# eBOOK_v33.net
KiCad netlist of a schematic drawn in EAGLE
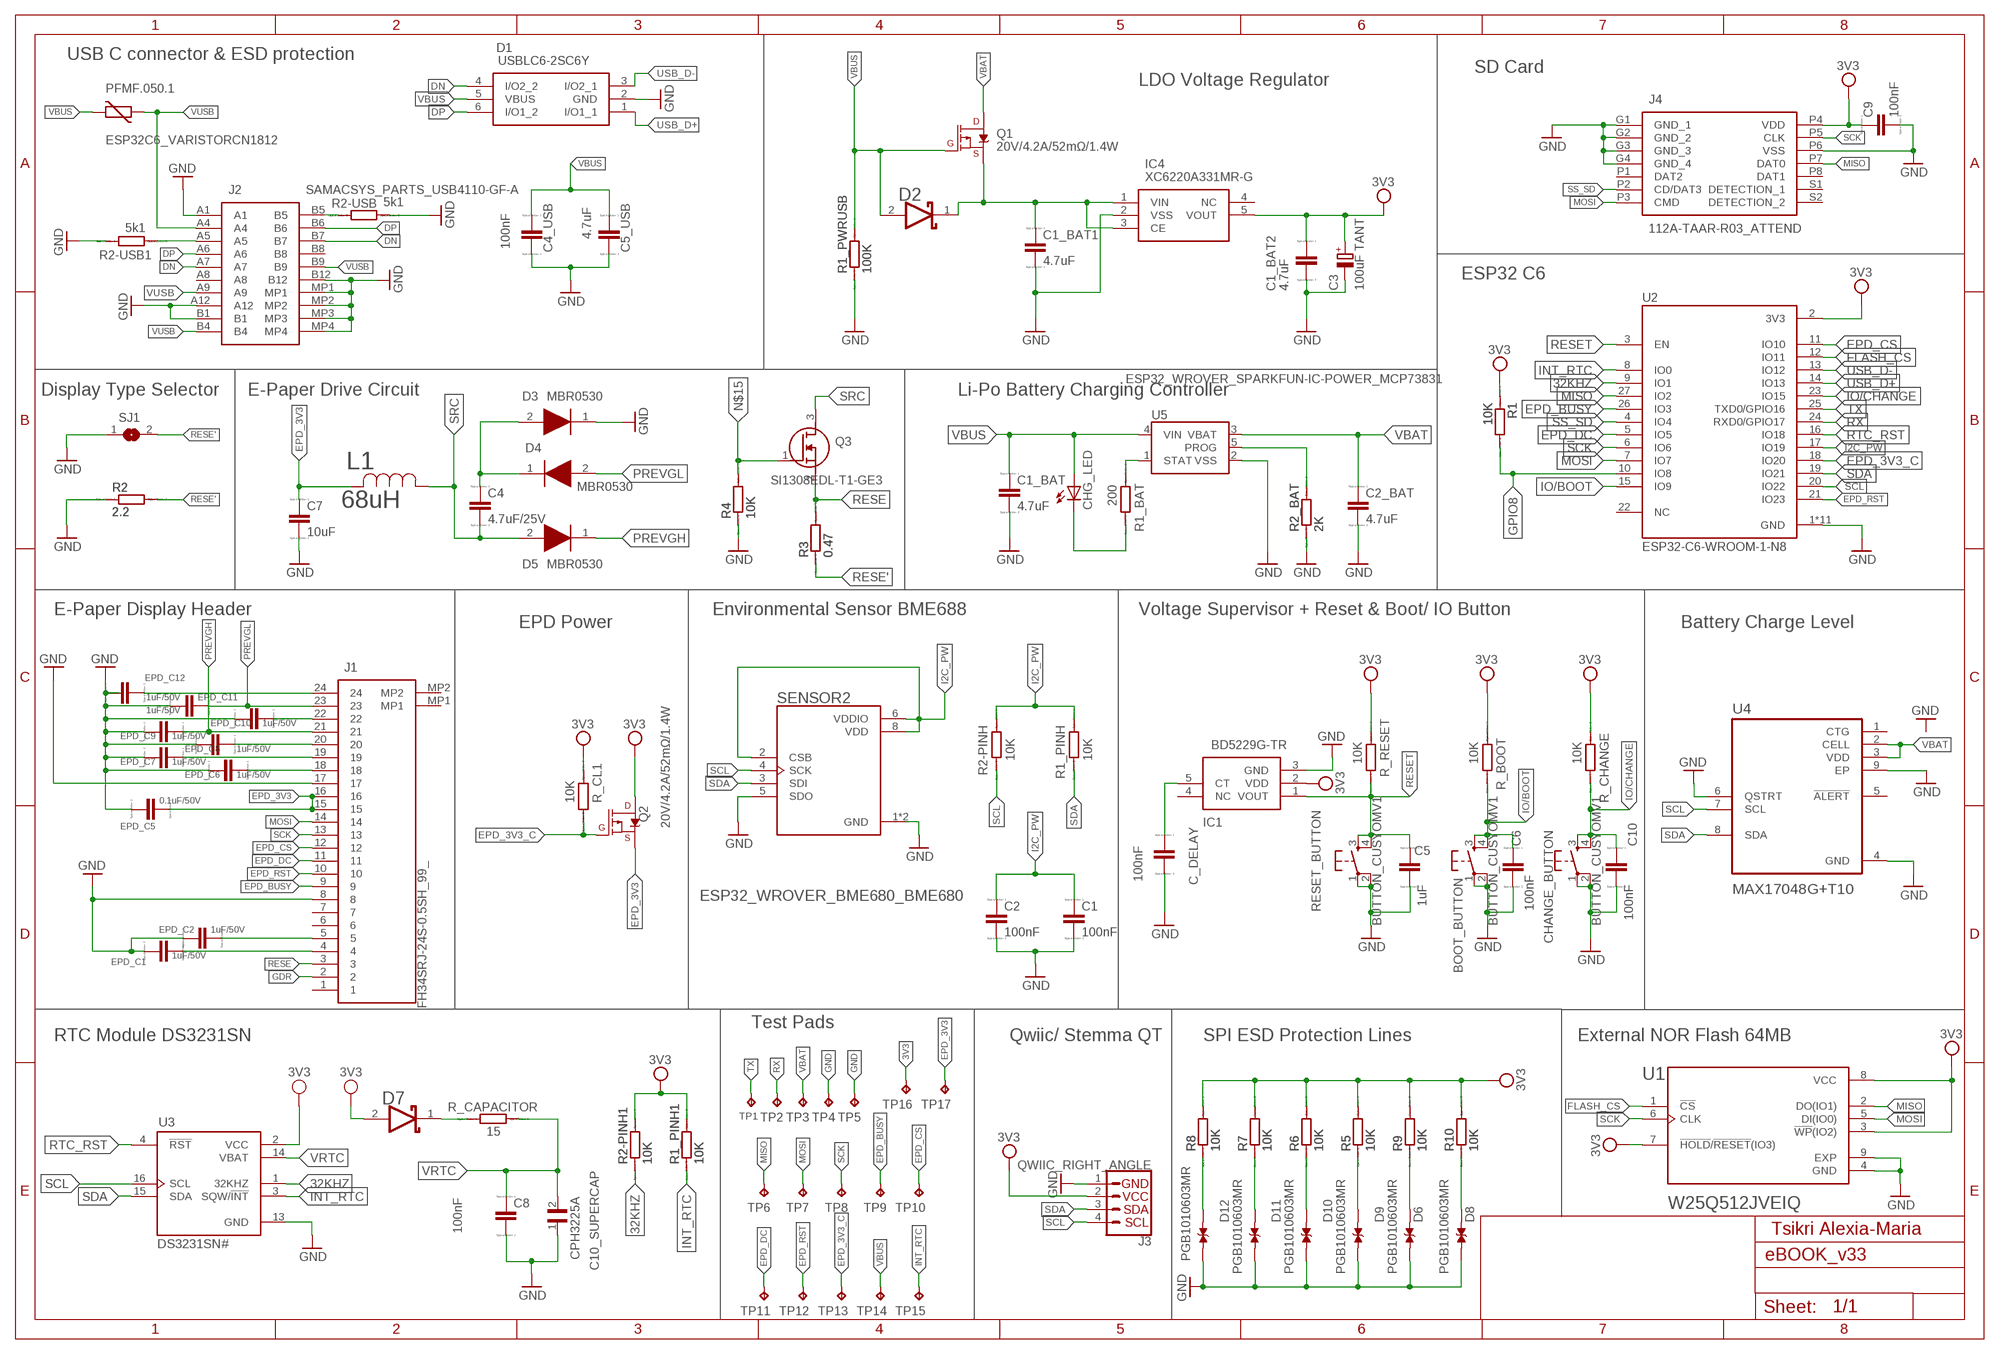
[diagram p0: schematic, sheet 1]

(export (version "E")
  (design (tool "Eeschema 10.0.6"))
  (components
    (comp (ref "BOOT_BUTTON")
      (value "BUTTON_CUSYOMV1")
      (footprint "eagle-import:MYBUTTON")
      (libsource (lib "eagle-import") (part "BUTTON_CUSYOMV1"))
    )
    (comp (ref "C1")
      (value "100nF")
      (footprint "eagle-import:ESP32_WROVER_EAGLE-LTSPICE_C0402")
      (libsource (lib "eagle-import") (part "ESP32_WROVER_EAGLE-LTSPICE_CC0402"))
    )
    (comp (ref "C1_BAT")
      (value "4.7uF")
      (footprint "eagle-import:ESP32_WROVER_EAGLE-LTSPICE_C0402")
      (libsource (lib "eagle-import") (part "ESP32_WROVER_EAGLE-LTSPICE_CC0402"))
    )
    (comp (ref "C1_BAT1")
      (value "4.7uF")
      (footprint "eagle-import:ESP32_WROVER_EAGLE-LTSPICE_C0402")
      (libsource (lib "eagle-import") (part "ESP32_WROVER_EAGLE-LTSPICE_CC0402"))
    )
    (comp (ref "C1_BAT2")
      (value "4.7uF")
      (footprint "eagle-import:ESP32_WROVER_EAGLE-LTSPICE_C0402")
      (libsource (lib "eagle-import") (part "ESP32_WROVER_EAGLE-LTSPICE_CC0402"))
    )
    (comp (ref "C2")
      (value "100nF")
      (footprint "eagle-import:ESP32_WROVER_EAGLE-LTSPICE_C0402")
      (libsource (lib "eagle-import") (part "ESP32_WROVER_EAGLE-LTSPICE_CC0402"))
    )
    (comp (ref "C2_BAT")
      (value "4.7uF")
      (footprint "eagle-import:ESP32_WROVER_EAGLE-LTSPICE_C0402")
      (libsource (lib "eagle-import") (part "ESP32_WROVER_EAGLE-LTSPICE_CC0402"))
    )
    (comp (ref "C3")
      (value "100uF TANT")
      (footprint "eagle-import:RCL_CT3528")
      (libsource (lib "eagle-import") (part "RCL_CPOL-EUCT3528"))
    )
    (comp (ref "C4")
      (value "4.7uF/25V")
      (footprint "eagle-import:ESP32_WROVER_EAGLE-LTSPICE_C0402")
      (libsource (lib "eagle-import") (part "ESP32_WROVER_EAGLE-LTSPICE_CC0402"))
    )
    (comp (ref "C4_USB")
      (value "100nF")
      (footprint "eagle-import:ESP32_WROVER_EAGLE-LTSPICE_C0402")
      (libsource (lib "eagle-import") (part "ESP32_WROVER_EAGLE-LTSPICE_CC0402"))
    )
    (comp (ref "C5")
      (value "1uF")
      (footprint "eagle-import:ESP32_WROVER_EAGLE-LTSPICE_C0402")
      (libsource (lib "eagle-import") (part "ESP32_WROVER_EAGLE-LTSPICE_CC0402"))
    )
    (comp (ref "C5_USB")
      (value "4.7uF")
      (footprint "eagle-import:ESP32_WROVER_EAGLE-LTSPICE_C0402")
      (libsource (lib "eagle-import") (part "ESP32_WROVER_EAGLE-LTSPICE_CC0402"))
    )
    (comp (ref "C6")
      (value "100nF")
      (footprint "eagle-import:ESP32_WROVER_EAGLE-LTSPICE_C0402")
      (libsource (lib "eagle-import") (part "ESP32_WROVER_EAGLE-LTSPICE_CC0402"))
    )
    (comp (ref "C7")
      (value "10uF")
      (footprint "eagle-import:ESP32_WROVER_EAGLE-LTSPICE_C0402")
      (libsource (lib "eagle-import") (part "ESP32_WROVER_EAGLE-LTSPICE_CC0402"))
    )
    (comp (ref "C8")
      (value "100nF")
      (footprint "eagle-import:ESP32_WROVER_EAGLE-LTSPICE_C0402")
      (libsource (lib "eagle-import") (part "ESP32_WROVER_EAGLE-LTSPICE_CC0402"))
    )
    (comp (ref "C9")
      (value "100nF")
      (footprint "eagle-import:ESP32_WROVER_EAGLE-LTSPICE_C0402")
      (libsource (lib "eagle-import") (part "ESP32_WROVER_EAGLE-LTSPICE_CC0402"))
    )
    (comp (ref "C10")
      (value "100nF")
      (footprint "eagle-import:ESP32_WROVER_EAGLE-LTSPICE_C0402")
      (libsource (lib "eagle-import") (part "ESP32_WROVER_EAGLE-LTSPICE_CC0402"))
    )
    (comp (ref "C10_SUPERCAP")
      (value "CPH3225A")
      (footprint "eagle-import:CAPCP3225X100N")
      (fields (field (name "MF") "Seiko Instruments"))
      (libsource (lib "eagle-import") (part "CPH3225A"))
    )
    (comp (ref "CHANGE_BUTTON")
      (value "BUTTON_CUSYOMV1")
      (footprint "eagle-import:MYBUTTON")
      (libsource (lib "eagle-import") (part "BUTTON_CUSYOMV1"))
    )
    (comp (ref "CHG_LED")
      (value "ADAFRUIT_LEDCHIP-LED0603")
      (footprint "eagle-import:ADAFRUIT_CHIP-LED0603")
      (libsource (lib "eagle-import") (part "ADAFRUIT_LEDCHIP-LED0603"))
    )
    (comp (ref "C_DELAY")
      (value "100nF")
      (footprint "eagle-import:ESP32_WROVER_EAGLE-LTSPICE_C0402")
      (libsource (lib "eagle-import") (part "ESP32_WROVER_EAGLE-LTSPICE_CC0402"))
    )
    (comp (ref "D1")
      (value "USBLC6-2SC6Y")
      (footprint "eagle-import:SOT95P280X145-6N")
      (fields (field (name "MF") "STMicroelectronics"))
      (libsource (lib "eagle-import") (part "USBLC6-2SC6Y"))
    )
    (comp (ref "D2")
      (value "ESP32_WROVER_AVX---SD0805S020S1R0_AVX_SD0805S020S1R0_0_0AVX_SD0805S020S1R0_0_0")
      (footprint "eagle-import:ESP32_WROVER_AVX---SD0805S020S1R0_AVX_SD0805S020S1R0_0")
      (fields
        (field (name "DIGIKEY_PART_NUMBER") "478-7800-1-ND")
        (field (name "MF") "AVX")
        (field (name "MOUSER_PART_NUMBER") "581-SD0805S020S1R0")
      )
      (libsource (lib "eagle-import") (part "ESP32_WROVER_AVX---SD0805S020S1R0_AVX_SD0805S020S1R0_0_0AVX_SD0805S020S1R0_0_0"))
    )
    (comp (ref "D3")
      (value "MBR0530")
      (footprint "eagle-import:SOD3716X135N")
      (fields (field (name "MF") "ON Semiconductor"))
      (libsource (lib "eagle-import") (part "MBR0530"))
    )
    (comp (ref "D4")
      (value "MBR0530")
      (footprint "eagle-import:SOD3716X135N")
      (fields (field (name "MF") "ON Semiconductor"))
      (libsource (lib "eagle-import") (part "MBR0530"))
    )
    (comp (ref "D5")
      (value "MBR0530")
      (footprint "eagle-import:SOD3716X135N")
      (fields (field (name "MF") "ON Semiconductor"))
      (libsource (lib "eagle-import") (part "MBR0530"))
    )
    (comp (ref "D6")
      (value "PGB1010603MR")
      (footprint "eagle-import:DIOC1608X36N")
      (fields (field (name "MF") "Littelfuse Inc."))
      (libsource (lib "eagle-import") (part "PGB1010603MR"))
    )
    (comp (ref "D7")
      (value "ESP32_WROVER_AVX---SD0805S020S1R0_AVX_SD0805S020S1R0_0_0AVX_SD0805S020S1R0_0_0")
      (footprint "eagle-import:ESP32_WROVER_AVX---SD0805S020S1R0_AVX_SD0805S020S1R0_0")
      (fields
        (field (name "DIGIKEY_PART_NUMBER") "478-7800-1-ND")
        (field (name "MF") "AVX")
        (field (name "MOUSER_PART_NUMBER") "581-SD0805S020S1R0")
      )
      (libsource (lib "eagle-import") (part "ESP32_WROVER_AVX---SD0805S020S1R0_AVX_SD0805S020S1R0_0_0AVX_SD0805S020S1R0_0_0"))
    )
    (comp (ref "D8")
      (value "PGB1010603MR")
      (footprint "eagle-import:DIOC1608X36N")
      (fields (field (name "MF") "Littelfuse Inc."))
      (libsource (lib "eagle-import") (part "PGB1010603MR"))
    )
    (comp (ref "D9")
      (value "PGB1010603MR")
      (footprint "eagle-import:DIOC1608X36N")
      (fields (field (name "MF") "Littelfuse Inc."))
      (libsource (lib "eagle-import") (part "PGB1010603MR"))
    )
    (comp (ref "D10")
      (value "PGB1010603MR")
      (footprint "eagle-import:DIOC1608X36N")
      (fields (field (name "MF") "Littelfuse Inc."))
      (libsource (lib "eagle-import") (part "PGB1010603MR"))
    )
    (comp (ref "D11")
      (value "PGB1010603MR")
      (footprint "eagle-import:DIOC1608X36N")
      (fields (field (name "MF") "Littelfuse Inc."))
      (libsource (lib "eagle-import") (part "PGB1010603MR"))
    )
    (comp (ref "D12")
      (value "PGB1010603MR")
      (footprint "eagle-import:DIOC1608X36N")
      (fields (field (name "MF") "Littelfuse Inc."))
      (libsource (lib "eagle-import") (part "PGB1010603MR"))
    )
    (comp (ref "EPD_C1")
      (value "1uF/50V")
      (footprint "eagle-import:ESP32_WROVER_EAGLE-LTSPICE_C0402")
      (libsource (lib "eagle-import") (part "ESP32_WROVER_EAGLE-LTSPICE_CC0402"))
    )
    (comp (ref "EPD_C2")
      (value "1uF/50V")
      (footprint "eagle-import:ESP32_WROVER_EAGLE-LTSPICE_C0402")
      (libsource (lib "eagle-import") (part "ESP32_WROVER_EAGLE-LTSPICE_CC0402"))
    )
    (comp (ref "EPD_C5")
      (value "0.1uF/50V")
      (footprint "eagle-import:ESP32_WROVER_EAGLE-LTSPICE_C0402")
      (libsource (lib "eagle-import") (part "ESP32_WROVER_EAGLE-LTSPICE_CC0402"))
    )
    (comp (ref "EPD_C6")
      (value "1uF/50V")
      (footprint "eagle-import:ESP32_WROVER_EAGLE-LTSPICE_C0402")
      (libsource (lib "eagle-import") (part "ESP32_WROVER_EAGLE-LTSPICE_CC0402"))
    )
    (comp (ref "EPD_C7")
      (value "1uF/50V")
      (footprint "eagle-import:ESP32_WROVER_EAGLE-LTSPICE_C0402")
      (libsource (lib "eagle-import") (part "ESP32_WROVER_EAGLE-LTSPICE_CC0402"))
    )
    (comp (ref "EPD_C8")
      (value "1uF/50V")
      (footprint "eagle-import:ESP32_WROVER_EAGLE-LTSPICE_C0402")
      (libsource (lib "eagle-import") (part "ESP32_WROVER_EAGLE-LTSPICE_CC0402"))
    )
    (comp (ref "EPD_C9")
      (value "1uF/50V")
      (footprint "eagle-import:ESP32_WROVER_EAGLE-LTSPICE_C0402")
      (libsource (lib "eagle-import") (part "ESP32_WROVER_EAGLE-LTSPICE_CC0402"))
    )
    (comp (ref "EPD_C10")
      (value "1uF/50V")
      (footprint "eagle-import:ESP32_WROVER_EAGLE-LTSPICE_C0402")
      (libsource (lib "eagle-import") (part "ESP32_WROVER_EAGLE-LTSPICE_CC0402"))
    )
    (comp (ref "EPD_C11")
      (value "1uF/50V")
      (footprint "eagle-import:ESP32_WROVER_EAGLE-LTSPICE_C0402")
      (libsource (lib "eagle-import") (part "ESP32_WROVER_EAGLE-LTSPICE_CC0402"))
    )
    (comp (ref "EPD_C12")
      (value "1uF/50V")
      (footprint "eagle-import:ESP32_WROVER_EAGLE-LTSPICE_C0402")
      (libsource (lib "eagle-import") (part "ESP32_WROVER_EAGLE-LTSPICE_CC0402"))
    )
    (comp (ref "IC1")
      (value "BD5229G-TR")
      (footprint "eagle-import:SOT95P280X125-5N")
      (fields (field (name "MOUSER_PART_NUMBER") "755-BD5229G-TR"))
      (libsource (lib "eagle-import") (part "BD5229G-TR"))
    )
    (comp (ref "IC4")
      (value "XC6220A331MR-G")
      (footprint "eagle-import:SOT95P280X120-5N")
      (fields (field (name "MOUSER_PART_NUMBER") "865-XC6220A331MR-G"))
      (libsource (lib "eagle-import") (part "XC6220A331MR-G"))
    )
    (comp (ref "J1")
      (value "FH34SRJ-24S-0.5SH_99_")
      (footprint "eagle-import:FH34SRJ24S05SH99")
      (fields
        (field (name "MANUFACTURER_PART_NUMBER") "FH34SRJ-24S-0.5SH(99)")
        (field (name "MOUSER_PART_NUMBER") "798-FH34SRJ24S05SH99")
      )
      (libsource (lib "eagle-import") (part "FH34SRJ-24S-0.5SH_99_"))
    )
    (comp (ref "J2")
      (value "SAMACSYS_PARTS_USB4110-GF-A")
      (footprint "eagle-import:SAMACSYS_PARTS_USB4110GFA")
      (fields
        (field (name "MANUFACTURER_PART_NUMBER") "USB4110-GF-A")
        (field (name "MOUSER_PART_NUMBER") "640-USB4110-GF-A")
      )
      (libsource (lib "eagle-import") (part "SAMACSYS_PARTS_USB4110-GF-A"))
    )
    (comp (ref "J3")
      (value "QWIIC_RIGHT_ANGLE")
      (footprint "eagle-import:JST04_1MM_RA")
      (libsource (lib "eagle-import") (part "QWIIC_CONNECTORJS-1MM"))
    )
    (comp (ref "J4")
      (value "112A-TAAR-R03_ATTEND")
      (footprint "eagle-import:112ATAARR03ATTEND")
      (fields (field (name "MANUFACTURER_PART_NUMBER") "112A-TAAR-R03 ATTEND"))
      (libsource (lib "eagle-import") (part "112A-TAAR-R03_ATTEND"))
    )
    (comp (ref "L1")
      (value "68uH")
      (footprint "eagle-import:IND_4828-WE-TPC_WRE")
      (fields
        (field (name "MANUFACTURER_PART_NUMBER") "744043680")
        (field (name "COPYRIGHT") "Copyright (C) 2024 Ultra Librarian. All rights reserved.")
      )
      (libsource (lib "eagle-import") (part "744043680IND_4828-WE-TPC_WRE"))
    )
    (comp (ref "PFMF.050.1")
      (value "ESP32C6_VARISTORCN1812")
      (footprint "eagle-import:ESP32C6_VARISTOR_CT_CN1812")
      (libsource (lib "eagle-import") (part "ESP32C6_VARISTORCN1812"))
    )
    (comp (ref "Q1")
      (value "20V/4.2A/52mΩ/1.4W")
      (footprint "eagle-import:ESP32_WROVER_SPARKFUN-DISCRETESEMI_SOT23-3")
      (libsource (lib "eagle-import") (part "ESP32_WROVER_SPARKFUN-DISCRETESEMI_MOSFET_PCH-DMG2305UX-7"))
    )
    (comp (ref "Q2")
      (value "20V/4.2A/52mΩ/1.4W")
      (footprint "eagle-import:ESP32_WROVER_SPARKFUN-DISCRETESEMI_SOT23-3")
      (libsource (lib "eagle-import") (part "ESP32_WROVER_SPARKFUN-DISCRETESEMI_MOSFET_PCH-DMG2305UX-7"))
    )
    (comp (ref "Q3")
      (value "SI1308EDL-T1-GE3")
      (footprint "eagle-import:SOT65P210X110-3N")
      (fields (field (name "MF") "Vishay Siliconix"))
      (libsource (lib "eagle-import") (part "SI1308EDL-T1-GE3"))
    )
    (comp (ref "R1")
      (value "10K")
      (footprint "eagle-import:ESP32_WROVER_EAGLE-LTSPICE_R0402")
      (libsource (lib "eagle-import") (part "ESP32_WROVER_EAGLE-LTSPICE_RR0402"))
    )
    (comp (ref "R1_BAT")
      (value "200")
      (footprint "eagle-import:ESP32_WROVER_EAGLE-LTSPICE_R0402")
      (libsource (lib "eagle-import") (part "ESP32_WROVER_EAGLE-LTSPICE_RR0402"))
    )
    (comp (ref "R1_PINH")
      (value "10K")
      (footprint "eagle-import:ESP32_WROVER_EAGLE-LTSPICE_R0402")
      (libsource (lib "eagle-import") (part "ESP32_WROVER_EAGLE-LTSPICE_RR0402"))
    )
    (comp (ref "R1_PINH1")
      (value "10K")
      (footprint "eagle-import:ESP32_WROVER_EAGLE-LTSPICE_R0402")
      (libsource (lib "eagle-import") (part "ESP32_WROVER_EAGLE-LTSPICE_RR0402"))
    )
    (comp (ref "R1_PWRUSB")
      (value "100K")
      (footprint "eagle-import:ESP32_WROVER_EAGLE-LTSPICE_R0402")
      (libsource (lib "eagle-import") (part "ESP32_WROVER_EAGLE-LTSPICE_RR0402"))
    )
    (comp (ref "R2")
      (value "2.2")
      (footprint "eagle-import:ESP32_WROVER_EAGLE-LTSPICE_R0402")
      (libsource (lib "eagle-import") (part "ESP32_WROVER_EAGLE-LTSPICE_RR0402"))
    )
    (comp (ref "R2-PINH")
      (value "10K")
      (footprint "eagle-import:ESP32_WROVER_EAGLE-LTSPICE_R0402")
      (libsource (lib "eagle-import") (part "ESP32_WROVER_EAGLE-LTSPICE_RR0402"))
    )
    (comp (ref "R2-PINH1")
      (value "10K")
      (footprint "eagle-import:ESP32_WROVER_EAGLE-LTSPICE_R0402")
      (libsource (lib "eagle-import") (part "ESP32_WROVER_EAGLE-LTSPICE_RR0402"))
    )
    (comp (ref "R2-USB")
      (value "5k1")
      (footprint "eagle-import:ESP32_WROVER_EAGLE-LTSPICE_R0402")
      (libsource (lib "eagle-import") (part "ESP32_WROVER_EAGLE-LTSPICE_RR0402"))
    )
    (comp (ref "R2-USB1")
      (value "5k1")
      (footprint "eagle-import:ESP32_WROVER_EAGLE-LTSPICE_R0402")
      (libsource (lib "eagle-import") (part "ESP32_WROVER_EAGLE-LTSPICE_RR0402"))
    )
    (comp (ref "R2_BAT")
      (value "2K")
      (footprint "eagle-import:ESP32_WROVER_EAGLE-LTSPICE_R0402")
      (libsource (lib "eagle-import") (part "ESP32_WROVER_EAGLE-LTSPICE_RR0402"))
    )
    (comp (ref "R3")
      (value "0.47")
      (footprint "eagle-import:ESP32_WROVER_EAGLE-LTSPICE_R0402")
      (libsource (lib "eagle-import") (part "ESP32_WROVER_EAGLE-LTSPICE_RR0402"))
    )
    (comp (ref "R4")
      (value "10K")
      (footprint "eagle-import:ESP32_WROVER_EAGLE-LTSPICE_R0402")
      (libsource (lib "eagle-import") (part "ESP32_WROVER_EAGLE-LTSPICE_RR0402"))
    )
    (comp (ref "R5")
      (value "10K")
      (footprint "eagle-import:ESP32_WROVER_EAGLE-LTSPICE_R0402")
      (libsource (lib "eagle-import") (part "ESP32_WROVER_EAGLE-LTSPICE_RR0402"))
    )
    (comp (ref "R6")
      (value "10K")
      (footprint "eagle-import:ESP32_WROVER_EAGLE-LTSPICE_R0402")
      (libsource (lib "eagle-import") (part "ESP32_WROVER_EAGLE-LTSPICE_RR0402"))
    )
    (comp (ref "R7")
      (value "10K")
      (footprint "eagle-import:ESP32_WROVER_EAGLE-LTSPICE_R0402")
      (libsource (lib "eagle-import") (part "ESP32_WROVER_EAGLE-LTSPICE_RR0402"))
    )
    (comp (ref "R8")
      (value "10K")
      (footprint "eagle-import:ESP32_WROVER_EAGLE-LTSPICE_R0402")
      (libsource (lib "eagle-import") (part "ESP32_WROVER_EAGLE-LTSPICE_RR0402"))
    )
    (comp (ref "R9")
      (value "10K")
      (footprint "eagle-import:ESP32_WROVER_EAGLE-LTSPICE_R0402")
      (libsource (lib "eagle-import") (part "ESP32_WROVER_EAGLE-LTSPICE_RR0402"))
    )
    (comp (ref "R10")
      (value "10K")
      (footprint "eagle-import:ESP32_WROVER_EAGLE-LTSPICE_R0402")
      (libsource (lib "eagle-import") (part "ESP32_WROVER_EAGLE-LTSPICE_RR0402"))
    )
    (comp (ref "RESET_BUTTON")
      (value "BUTTON_CUSYOMV1")
      (footprint "eagle-import:MYBUTTON")
      (libsource (lib "eagle-import") (part "BUTTON_CUSYOMV1"))
    )
    (comp (ref "R_BOOT")
      (value "10K")
      (footprint "eagle-import:ESP32_WROVER_EAGLE-LTSPICE_R0402")
      (libsource (lib "eagle-import") (part "ESP32_WROVER_EAGLE-LTSPICE_RR0402"))
    )
    (comp (ref "R_CAPACITOR")
      (value "15")
      (footprint "eagle-import:ESP32_WROVER_EAGLE-LTSPICE_R0402")
      (libsource (lib "eagle-import") (part "ESP32_WROVER_EAGLE-LTSPICE_RR0402"))
    )
    (comp (ref "R_CHANGE")
      (value "10K")
      (footprint "eagle-import:ESP32_WROVER_EAGLE-LTSPICE_R0402")
      (libsource (lib "eagle-import") (part "ESP32_WROVER_EAGLE-LTSPICE_RR0402"))
    )
    (comp (ref "R_CL1")
      (value "10K")
      (footprint "eagle-import:ESP32_WROVER_EAGLE-LTSPICE_R0402")
      (libsource (lib "eagle-import") (part "ESP32_WROVER_EAGLE-LTSPICE_RR0402"))
    )
    (comp (ref "R_RESET")
      (value "10K")
      (footprint "eagle-import:ESP32_WROVER_EAGLE-LTSPICE_R0402")
      (libsource (lib "eagle-import") (part "ESP32_WROVER_EAGLE-LTSPICE_RR0402"))
    )
    (comp (ref "SENSOR2")
      (value "ESP32_WROVER_BME680_BME680")
      (footprint "eagle-import:ESP32_WROVER_BME680_PSON80P300X300X100-8N")
      (fields (field (name "MF") "Bosch Sensortec") (field (name "MP") "BME680"))
      (libsource (lib "eagle-import") (part "ESP32_WROVER_BME680_BME680"))
    )
    (comp (ref "SJ1") (value "SJ") (footprint "eagle-import:SJ") (libsource (lib "eagle-import") (part "SJ")))
    (comp (ref "TP1")
      (value "TPTP20R")
      (footprint "eagle-import:TP20R")
      (libsource (lib "eagle-import") (part "TPTP20R"))
    )
    (comp (ref "TP2")
      (value "TPTP20R")
      (footprint "eagle-import:TP20R")
      (libsource (lib "eagle-import") (part "TPTP20R"))
    )
    (comp (ref "TP3")
      (value "TPTP20R")
      (footprint "eagle-import:TP20R")
      (libsource (lib "eagle-import") (part "TPTP20R"))
    )
    (comp (ref "TP4")
      (value "TPTP20R")
      (footprint "eagle-import:TP20R")
      (libsource (lib "eagle-import") (part "TPTP20R"))
    )
    (comp (ref "TP5")
      (value "TPTP20R")
      (footprint "eagle-import:TP20R")
      (libsource (lib "eagle-import") (part "TPTP20R"))
    )
    (comp (ref "TP6")
      (value "TPTP20R")
      (footprint "eagle-import:TP20R")
      (libsource (lib "eagle-import") (part "TPTP20R"))
    )
    (comp (ref "TP7")
      (value "TPTP20R")
      (footprint "eagle-import:TP20R")
      (libsource (lib "eagle-import") (part "TPTP20R"))
    )
    (comp (ref "TP8")
      (value "TPTP20R")
      (footprint "eagle-import:TP20R")
      (libsource (lib "eagle-import") (part "TPTP20R"))
    )
    (comp (ref "TP9")
      (value "TPTP20R")
      (footprint "eagle-import:TP20R")
      (libsource (lib "eagle-import") (part "TPTP20R"))
    )
    (comp (ref "TP10")
      (value "TPTP20R")
      (footprint "eagle-import:TP20R")
      (libsource (lib "eagle-import") (part "TPTP20R"))
    )
    (comp (ref "TP11")
      (value "TPTP20R")
      (footprint "eagle-import:TP20R")
      (libsource (lib "eagle-import") (part "TPTP20R"))
    )
    (comp (ref "TP12")
      (value "TPTP20R")
      (footprint "eagle-import:TP20R")
      (libsource (lib "eagle-import") (part "TPTP20R"))
    )
    (comp (ref "TP13")
      (value "TPTP20R")
      (footprint "eagle-import:TP20R")
      (libsource (lib "eagle-import") (part "TPTP20R"))
    )
    (comp (ref "TP14")
      (value "TPTP20R")
      (footprint "eagle-import:TP20R")
      (libsource (lib "eagle-import") (part "TPTP20R"))
    )
    (comp (ref "TP15")
      (value "TPTP20R")
      (footprint "eagle-import:TP20R")
      (libsource (lib "eagle-import") (part "TPTP20R"))
    )
    (comp (ref "TP16")
      (value "TPTP20R")
      (footprint "eagle-import:TP20R")
      (libsource (lib "eagle-import") (part "TPTP20R"))
    )
    (comp (ref "TP17")
      (value "TPTP20R")
      (footprint "eagle-import:TP20R")
      (libsource (lib "eagle-import") (part "TPTP20R"))
    )
    (comp (ref "U1")
      (value "W25Q512JVEIQ")
      (footprint "eagle-import:SON127P600X800X80-9N")
      (fields (field (name "MF") "Winbond Electronics"))
      (libsource (lib "eagle-import") (part "W25Q512JVEIQ"))
    )
    (comp (ref "U2")
      (value "ESP32-C6-WROOM-1-N8")
      (footprint "eagle-import:XCVR_ESP32-C6-WROOM-1-N8")
      (fields (field (name "MF") "Espressif Systems"))
      (libsource (lib "eagle-import") (part "ESP32-C6-WROOM-1-N8"))
    )
    (comp (ref "U3")
      (value "DS3231SN#")
      (footprint "eagle-import:SOIC127P1032X265-16N")
      (fields (field (name "MF") "Maxim Integrated Products"))
      (libsource (lib "eagle-import") (part "DS3231SN#"))
    )
    (comp (ref "U4")
      (value "MAX17048G+T10")
      (footprint "eagle-import:SON50P200X200X80-9N")
      (fields (field (name "MF") "Analog Devices"))
      (libsource (lib "eagle-import") (part "MAX17048G+T10"))
    )
    (comp (ref "U5")
      (value "ESP32_WROVER_SPARKFUN-IC-POWER_MCP73831")
      (footprint "eagle-import:ESP32_WROVER_SPARKFUN-IC-POWER_SOT23-5")
      (libsource (lib "eagle-import") (part "ESP32_WROVER_SPARKFUN-IC-POWER_MCP73831"))
    )
  )
  (nets
    (net (code "1") (name "/CTG") (class "Default")
      (node (ref "U4") (pin "1") (pinfunction "CTG_1") (pintype "power_in"))
    )
    (net (code "2") (name "3V3") (class "Default")
      (node (ref "C1_BAT2") (pin "1") (pinfunction "1_1") (pintype "passive"))
      (node (ref "C3") (pin "+") (pinfunction "+_+") (pintype "passive"))
      (node (ref "C9") (pin "1") (pinfunction "1_1") (pintype "passive"))
      (node (ref "D7") (pin "2") (pinfunction "ANODE_2") (pintype "bidirectional"))
      (node (ref "IC1") (pin "2") (pinfunction "VDD_2") (pintype "bidirectional"))
      (node (ref "IC4") (pin "5") (pinfunction "VOUT_5") (pintype "bidirectional"))
      (node (ref "J3") (pin "2") (pinfunction "2_2") (pintype "power_in"))
      (node (ref "J4") (pin "P4") (pinfunction "VDD_P4") (pintype "bidirectional"))
      (node (ref "Q2") (pin "3") (pinfunction "D_3") (pintype "bidirectional"))
      (node (ref "R1") (pin "1") (pinfunction "1_1") (pintype "passive"))
      (node (ref "R10") (pin "2") (pinfunction "2_2") (pintype "passive"))
      (node (ref "R1_PINH1") (pin "2") (pinfunction "2_2") (pintype "passive"))
      (node (ref "R2-PINH1") (pin "2") (pinfunction "2_2") (pintype "passive"))
      (node (ref "R5") (pin "2") (pinfunction "2_2") (pintype "passive"))
      (node (ref "R6") (pin "2") (pinfunction "2_2") (pintype "passive"))
      (node (ref "R7") (pin "2") (pinfunction "2_2") (pintype "passive"))
      (node (ref "R8") (pin "2") (pinfunction "2_2") (pintype "passive"))
      (node (ref "R9") (pin "2") (pinfunction "2_2") (pintype "passive"))
      (node (ref "R_BOOT") (pin "2") (pinfunction "2_2") (pintype "passive"))
      (node (ref "R_CHANGE") (pin "2") (pinfunction "2_2") (pintype "passive"))
      (node (ref "R_CL1") (pin "2") (pinfunction "2_2") (pintype "passive"))
      (node (ref "R_RESET") (pin "2") (pinfunction "2_2") (pintype "passive"))
      (node (ref "TP16") (pin "TP") (pinfunction "TP_TP") (pintype "input"))
      (node (ref "U1") (pin "3") (pinfunction "~{WP}(IO2)_3") (pintype "bidirectional"))
      (node (ref "U1") (pin "7") (pinfunction "~{HOLD}/~{RESET}(IO3)_7") (pintype "bidirectional"))
      (node (ref "U1") (pin "8") (pinfunction "VCC_8") (pintype "power_in"))
      (node (ref "U2") (pin "2") (pinfunction "3V3_2") (pintype "power_in"))
      (node (ref "U3") (pin "2") (pinfunction "VCC_2") (pintype "power_in"))
    )
    (net (code "3") (name "32KHZ") (class "Default")
      (node (ref "R2-PINH1") (pin "1") (pinfunction "1_1") (pintype "passive"))
      (node (ref "U2") (pin "9") (pinfunction "IO1_9") (pintype "bidirectional"))
      (node (ref "U3") (pin "1") (pinfunction "32KHZ_1") (pintype "output"))
    )
    (net (code "4") (name "DN") (class "Default")
      (node (ref "D1") (pin "4") (pinfunction "I/O2_2_4") (pintype "bidirectional"))
      (node (ref "J2") (pin "A7") (pinfunction "A7_A7") (pintype "bidirectional"))
      (node (ref "J2") (pin "B7") (pinfunction "B7_B7") (pintype "bidirectional"))
    )
    (net (code "5") (name "DP") (class "Default")
      (node (ref "D1") (pin "6") (pinfunction "I/O1_2_6") (pintype "bidirectional"))
      (node (ref "J2") (pin "A6") (pinfunction "A6_A6") (pintype "bidirectional"))
      (node (ref "J2") (pin "B6") (pinfunction "B6_B6") (pintype "bidirectional"))
    )
    (net (code "6") (name "EPD_3V3") (class "Default")
      (node (ref "C7") (pin "1") (pinfunction "1_1") (pintype "passive"))
      (node (ref "EPD_C5") (pin "1") (pinfunction "1_1") (pintype "passive"))
      (node (ref "J1") (pin "15") (pinfunction "15_15") (pintype "bidirectional"))
      (node (ref "J1") (pin "16") (pinfunction "16_16") (pintype "bidirectional"))
      (node (ref "L1") (pin "2") (pinfunction "2_2") (pintype "passive"))
      (node (ref "Q2") (pin "2") (pinfunction "S_2") (pintype "bidirectional"))
      (node (ref "TP17") (pin "TP") (pinfunction "TP_TP") (pintype "input"))
    )
    (net (code "7") (name "EPD_3V3_C") (class "Default")
      (node (ref "Q2") (pin "1") (pinfunction "G_1") (pintype "bidirectional"))
      (node (ref "R_CL1") (pin "1") (pinfunction "1_1") (pintype "passive"))
      (node (ref "TP13") (pin "TP") (pinfunction "TP_TP") (pintype "input"))
      (node (ref "U2") (pin "18") (pinfunction "IO20_18") (pintype "bidirectional"))
    )
    (net (code "8") (name "EPD_BUSY") (class "Default")
      (node (ref "J1") (pin "9") (pinfunction "9_9") (pintype "bidirectional"))
      (node (ref "TP9") (pin "TP") (pinfunction "TP_TP") (pintype "input"))
      (node (ref "U2") (pin "26") (pinfunction "IO3_26") (pintype "bidirectional"))
    )
    (net (code "9") (name "EPD_CS") (class "Default")
      (node (ref "J1") (pin "12") (pinfunction "12_12") (pintype "bidirectional"))
      (node (ref "TP10") (pin "TP") (pinfunction "TP_TP") (pintype "input"))
      (node (ref "U2") (pin "11") (pinfunction "IO10_11") (pintype "bidirectional"))
    )
    (net (code "10") (name "EPD_DC") (class "Default")
      (node (ref "J1") (pin "11") (pinfunction "11_11") (pintype "bidirectional"))
      (node (ref "TP11") (pin "TP") (pinfunction "TP_TP") (pintype "input"))
      (node (ref "U2") (pin "5") (pinfunction "IO5_5") (pintype "bidirectional"))
    )
    (net (code "11") (name "EPD_RST") (class "Default")
      (node (ref "J1") (pin "10") (pinfunction "10_10") (pintype "bidirectional"))
      (node (ref "TP12") (pin "TP") (pinfunction "TP_TP") (pintype "input"))
      (node (ref "U2") (pin "21") (pinfunction "IO23_21") (pintype "bidirectional"))
    )
    (net (code "12") (name "FLASH_CS") (class "Default")
      (node (ref "U1") (pin "1") (pinfunction "~{CS}_1") (pintype "input"))
      (node (ref "U2") (pin "12") (pinfunction "IO11_12") (pintype "bidirectional"))
    )
    (net (code "13") (name "GDR") (class "Default")
      (node (ref "J1") (pin "2") (pinfunction "2_2") (pintype "bidirectional"))
    )
    (net (code "14") (name "GND") (class "Default")
      (node (ref "BOOT_BUTTON") (pin "1") (pinfunction "1_1") (pintype "passive"))
      (node (ref "BOOT_BUTTON") (pin "2") (pinfunction "2_2") (pintype "passive"))
      (node (ref "C1") (pin "2") (pinfunction "2_2") (pintype "passive"))
      (node (ref "C10") (pin "2") (pinfunction "2_2") (pintype "passive"))
      (node (ref "C10_SUPERCAP") (pin "1") (pinfunction "1_1") (pintype "passive"))
      (node (ref "C1_BAT") (pin "2") (pinfunction "2_2") (pintype "passive"))
      (node (ref "C1_BAT1") (pin "2") (pinfunction "2_2") (pintype "passive"))
      (node (ref "C1_BAT2") (pin "2") (pinfunction "2_2") (pintype "passive"))
      (node (ref "C2") (pin "2") (pinfunction "2_2") (pintype "passive"))
      (node (ref "C2_BAT") (pin "2") (pinfunction "2_2") (pintype "passive"))
      (node (ref "C3") (pin "-") (pinfunction "-_-") (pintype "passive"))
      (node (ref "C4_USB") (pin "2") (pinfunction "2_2") (pintype "passive"))
      (node (ref "C5") (pin "2") (pinfunction "2_2") (pintype "passive"))
      (node (ref "C5_USB") (pin "2") (pinfunction "2_2") (pintype "passive"))
      (node (ref "C6") (pin "2") (pinfunction "2_2") (pintype "passive"))
      (node (ref "C7") (pin "2") (pinfunction "2_2") (pintype "passive"))
      (node (ref "C8") (pin "2") (pinfunction "2_2") (pintype "passive"))
      (node (ref "C9") (pin "2") (pinfunction "2_2") (pintype "passive"))
      (node (ref "CHANGE_BUTTON") (pin "1") (pinfunction "1_1") (pintype "passive"))
      (node (ref "CHANGE_BUTTON") (pin "2") (pinfunction "2_2") (pintype "passive"))
      (node (ref "C_DELAY") (pin "2") (pinfunction "2_2") (pintype "passive"))
      (node (ref "D1") (pin "2") (pinfunction "GND_2") (pintype "bidirectional"))
      (node (ref "D10") (pin "1") (pinfunction "1_1") (pintype "passive"))
      (node (ref "D11") (pin "1") (pinfunction "1_1") (pintype "passive"))
      (node (ref "D12") (pin "1") (pinfunction "1_1") (pintype "passive"))
      (node (ref "D3") (pin "1") (pinfunction "K_1") (pintype "bidirectional"))
      (node (ref "D6") (pin "1") (pinfunction "1_1") (pintype "passive"))
      (node (ref "D8") (pin "1") (pinfunction "1_1") (pintype "passive"))
      (node (ref "D9") (pin "1") (pinfunction "1_1") (pintype "passive"))
      (node (ref "EPD_C1") (pin "2") (pinfunction "2_2") (pintype "passive"))
      (node (ref "EPD_C10") (pin "2") (pinfunction "2_2") (pintype "passive"))
      (node (ref "EPD_C11") (pin "2") (pinfunction "2_2") (pintype "passive"))
      (node (ref "EPD_C12") (pin "2") (pinfunction "2_2") (pintype "passive"))
      (node (ref "EPD_C2") (pin "2") (pinfunction "2_2") (pintype "passive"))
      (node (ref "EPD_C5") (pin "2") (pinfunction "2_2") (pintype "passive"))
      (node (ref "EPD_C6") (pin "2") (pinfunction "2_2") (pintype "passive"))
      (node (ref "EPD_C7") (pin "2") (pinfunction "2_2") (pintype "passive"))
      (node (ref "EPD_C8") (pin "2") (pinfunction "2_2") (pintype "passive"))
      (node (ref "EPD_C9") (pin "2") (pinfunction "2_2") (pintype "passive"))
      (node (ref "IC1") (pin "3") (pinfunction "GND_3") (pintype "bidirectional"))
      (node (ref "IC4") (pin "2") (pinfunction "VSS_2") (pintype "bidirectional"))
      (node (ref "J1") (pin "17") (pinfunction "17_17") (pintype "bidirectional"))
      (node (ref "J1") (pin "8") (pinfunction "8_8") (pintype "bidirectional"))
      (node (ref "J2") (pin "A1") (pinfunction "A1_A1") (pintype "bidirectional"))
      (node (ref "J2") (pin "A12") (pinfunction "A12_A12") (pintype "bidirectional"))
      (node (ref "J2") (pin "B1") (pinfunction "B1_B1") (pintype "bidirectional"))
      (node (ref "J2") (pin "B12") (pinfunction "B12_B12") (pintype "bidirectional"))
      (node (ref "J2") (pin "MP1") (pinfunction "MP1_MP1") (pintype "bidirectional"))
      (node (ref "J2") (pin "MP2") (pinfunction "MP2_MP2") (pintype "bidirectional"))
      (node (ref "J2") (pin "MP3") (pinfunction "MP3_MP3") (pintype "bidirectional"))
      (node (ref "J2") (pin "MP4") (pinfunction "MP4_MP4") (pintype "bidirectional"))
      (node (ref "J3") (pin "1") (pinfunction "1_1") (pintype "power_in"))
      (node (ref "J4") (pin "G1") (pinfunction "GND_1_G1") (pintype "bidirectional"))
      (node (ref "J4") (pin "G2") (pinfunction "GND_2_G2") (pintype "bidirectional"))
      (node (ref "J4") (pin "G3") (pinfunction "GND_3_G3") (pintype "bidirectional"))
      (node (ref "J4") (pin "G4") (pinfunction "GND_4_G4") (pintype "bidirectional"))
      (node (ref "J4") (pin "P6") (pinfunction "VSS_P6") (pintype "bidirectional"))
      (node (ref "R1_PWRUSB") (pin "1") (pinfunction "1_1") (pintype "passive"))
      (node (ref "R2") (pin "1") (pinfunction "1_1") (pintype "passive"))
      (node (ref "R2-USB") (pin "2") (pinfunction "2_2") (pintype "passive"))
      (node (ref "R2-USB1") (pin "1") (pinfunction "1_1") (pintype "passive"))
      (node (ref "R2_BAT") (pin "1") (pinfunction "1_1") (pintype "passive"))
      (node (ref "R4") (pin "1") (pinfunction "1_1") (pintype "passive"))
      (node (ref "RESET_BUTTON") (pin "1") (pinfunction "1_1") (pintype "passive"))
      (node (ref "RESET_BUTTON") (pin "2") (pinfunction "2_2") (pintype "passive"))
      (node (ref "SENSOR2") (pin "1") (pinfunction "GND_1") (pintype "power_in"))
      (node (ref "SENSOR2") (pin "5") (pinfunction "SDO_5") (pintype "bidirectional"))
      (node (ref "SENSOR2") (pin "7") (pinfunction "GND_7") (pintype "power_in"))
      (node (ref "SJ1") (pin "1") (pinfunction "1_1") (pintype "passive"))
      (node (ref "TP4") (pin "TP") (pinfunction "TP_TP") (pintype "input"))
      (node (ref "TP5") (pin "TP") (pinfunction "TP_TP") (pintype "input"))
      (node (ref "U1") (pin "4") (pinfunction "GND_4") (pintype "power_in"))
      (node (ref "U1") (pin "9") (pinfunction "EXP_9") (pintype "passive"))
      (node (ref "U2") (pin "1") (pinfunction "GND_1") (pintype "power_in"))
      (node (ref "U2") (pin "28") (pinfunction "GND_28") (pintype "power_in"))
      (node (ref "U2") (pin "29_1") (pinfunction "GND_29_1") (pintype "power_in"))
      (node (ref "U2") (pin "29_2") (pinfunction "GND_29_2") (pintype "power_in"))
      (node (ref "U2") (pin "29_3") (pinfunction "GND_29_3") (pintype "power_in"))
      (node (ref "U2") (pin "29_4") (pinfunction "GND_29_4") (pintype "power_in"))
      (node (ref "U2") (pin "29_5") (pinfunction "GND_29_5") (pintype "power_in"))
      (node (ref "U2") (pin "29_6") (pinfunction "GND_29_6") (pintype "power_in"))
      (node (ref "U2") (pin "29_7") (pinfunction "GND_29_7") (pintype "power_in"))
      (node (ref "U2") (pin "29_8") (pinfunction "GND_29_8") (pintype "power_in"))
      (node (ref "U2") (pin "29_9") (pinfunction "GND_29_9") (pintype "power_in"))
      (node (ref "U3") (pin "13") (pinfunction "GND_13") (pintype "power_in"))
      (node (ref "U4") (pin "4") (pinfunction "GND_4") (pintype "power_in"))
      (node (ref "U4") (pin "6") (pinfunction "QSTRT_6") (pintype "input"))
      (node (ref "U4") (pin "9") (pinfunction "EP_9") (pintype "power_in"))
      (node (ref "U5") (pin "2") (pinfunction "VSS_2") (pintype "power_in"))
    )
    (net (code "15") (name "GPIO8") (class "Default")
      (node (ref "R1") (pin "2") (pinfunction "2_2") (pintype "passive"))
      (node (ref "U2") (pin "10") (pinfunction "IO8_10") (pintype "bidirectional"))
    )
    (net (code "16") (name "I2C_PW") (class "Default")
      (node (ref "C1") (pin "1") (pinfunction "1_1") (pintype "passive"))
      (node (ref "C2") (pin "1") (pinfunction "1_1") (pintype "passive"))
      (node (ref "R1_PINH") (pin "1") (pinfunction "1_1") (pintype "passive"))
      (node (ref "R2-PINH") (pin "1") (pinfunction "1_1") (pintype "passive"))
      (node (ref "SENSOR2") (pin "2") (pinfunction "CSB_2") (pintype "input"))
      (node (ref "SENSOR2") (pin "6") (pinfunction "VDDIO_6") (pintype "power_in"))
      (node (ref "SENSOR2") (pin "8") (pinfunction "VDD_8") (pintype "power_in"))
      (node (ref "U2") (pin "17") (pinfunction "IO19_17") (pintype "bidirectional"))
    )
    (net (code "17") (name "INT_RTC") (class "Default")
      (node (ref "R1_PINH1") (pin "1") (pinfunction "1_1") (pintype "passive"))
      (node (ref "TP15") (pin "TP") (pinfunction "TP_TP") (pintype "input"))
      (node (ref "U2") (pin "8") (pinfunction "IO0_8") (pintype "bidirectional"))
      (node (ref "U3") (pin "3") (pinfunction "SQW/~{INT}_3") (pintype "output"))
    )
    (net (code "18") (name "IO{slash}BOOT") (class "Default")
      (node (ref "BOOT_BUTTON") (pin "3") (pinfunction "3_3") (pintype "passive"))
      (node (ref "BOOT_BUTTON") (pin "4") (pinfunction "4_4") (pintype "passive"))
      (node (ref "C6") (pin "1") (pinfunction "1_1") (pintype "passive"))
      (node (ref "R_BOOT") (pin "1") (pinfunction "1_1") (pintype "passive"))
      (node (ref "U2") (pin "15") (pinfunction "IO9_15") (pintype "bidirectional"))
    )
    (net (code "19") (name "IO{slash}CHANGE") (class "Default")
      (node (ref "C10") (pin "1") (pinfunction "1_1") (pintype "passive"))
      (node (ref "CHANGE_BUTTON") (pin "3") (pinfunction "3_3") (pintype "passive"))
      (node (ref "CHANGE_BUTTON") (pin "4") (pinfunction "4_4") (pintype "passive"))
      (node (ref "R_CHANGE") (pin "1") (pinfunction "1_1") (pintype "passive"))
      (node (ref "U2") (pin "23") (pinfunction "IO15_23") (pintype "bidirectional"))
    )
    (net (code "20") (name "MISO") (class "Default")
      (node (ref "J4") (pin "P7") (pinfunction "DAT0_P7") (pintype "bidirectional"))
      (node (ref "TP6") (pin "TP") (pinfunction "TP_TP") (pintype "input"))
      (node (ref "U1") (pin "2") (pinfunction "DO(IO1)_2") (pintype "bidirectional"))
      (node (ref "U2") (pin "27") (pinfunction "IO2_27") (pintype "bidirectional"))
    )
    (net (code "21") (name "MOSI") (class "Default")
      (node (ref "J1") (pin "14") (pinfunction "14_14") (pintype "bidirectional"))
      (node (ref "J4") (pin "P3") (pinfunction "CMD_P3") (pintype "bidirectional"))
      (node (ref "TP7") (pin "TP") (pinfunction "TP_TP") (pintype "input"))
      (node (ref "U1") (pin "5") (pinfunction "DI(IO0)_5") (pintype "bidirectional"))
      (node (ref "U2") (pin "7") (pinfunction "IO7_7") (pintype "bidirectional"))
    )
    (net (code "22") (name "N$15") (class "Default")
      (node (ref "Q3") (pin "1") (pinfunction "G_1") (pintype "bidirectional"))
      (node (ref "R4") (pin "2") (pinfunction "2_2") (pintype "passive"))
    )
    (net (code "23") (name "Net-(CHG_LED-PadC)") (class "Default")
      (node (ref "CHG_LED") (pin "C") (pinfunction "C_C") (pintype "passive"))
      (node (ref "R1_BAT") (pin "1") (pinfunction "1_1") (pintype "passive"))
    )
    (net (code "24") (name "Net-(D2-CATHODE)") (class "Default")
      (node (ref "C1_BAT1") (pin "1") (pinfunction "1_1") (pintype "passive"))
      (node (ref "D2") (pin "1") (pinfunction "CATHODE_1") (pintype "bidirectional"))
      (node (ref "IC4") (pin "1") (pinfunction "VIN_1") (pintype "bidirectional"))
      (node (ref "IC4") (pin "3") (pinfunction "CE_3") (pintype "bidirectional"))
      (node (ref "Q1") (pin "2") (pinfunction "S_2") (pintype "bidirectional"))
    )
    (net (code "25") (name "Net-(D3-A)") (class "Default")
      (node (ref "C4") (pin "1") (pinfunction "1_1") (pintype "passive"))
      (node (ref "D3") (pin "2") (pinfunction "A_2") (pintype "bidirectional"))
      (node (ref "D4") (pin "1") (pinfunction "K_1") (pintype "bidirectional"))
    )
    (net (code "26") (name "Net-(D6-Pad2)") (class "Default")
      (node (ref "D6") (pin "2") (pinfunction "2_2") (pintype "passive"))
      (node (ref "R9") (pin "1") (pinfunction "1_1") (pintype "passive"))
    )
    (net (code "27") (name "Net-(D7-CATHODE)") (class "Default")
      (node (ref "D7") (pin "1") (pinfunction "CATHODE_1") (pintype "bidirectional"))
      (node (ref "R_CAPACITOR") (pin "1") (pinfunction "1_1") (pintype "passive"))
    )
    (net (code "28") (name "Net-(D8-Pad2)") (class "Default")
      (node (ref "D8") (pin "2") (pinfunction "2_2") (pintype "passive"))
      (node (ref "R10") (pin "1") (pinfunction "1_1") (pintype "passive"))
    )
    (net (code "29") (name "Net-(D9-Pad2)") (class "Default")
      (node (ref "D9") (pin "2") (pinfunction "2_2") (pintype "passive"))
      (node (ref "R5") (pin "1") (pinfunction "1_1") (pintype "passive"))
    )
    (net (code "30") (name "Net-(D10-Pad2)") (class "Default")
      (node (ref "D10") (pin "2") (pinfunction "2_2") (pintype "passive"))
      (node (ref "R6") (pin "1") (pinfunction "1_1") (pintype "passive"))
    )
    (net (code "31") (name "Net-(D11-Pad2)") (class "Default")
      (node (ref "D11") (pin "2") (pinfunction "2_2") (pintype "passive"))
      (node (ref "R7") (pin "1") (pinfunction "1_1") (pintype "passive"))
    )
    (net (code "32") (name "Net-(D12-Pad2)") (class "Default")
      (node (ref "D12") (pin "2") (pinfunction "2_2") (pintype "passive"))
      (node (ref "R8") (pin "1") (pinfunction "1_1") (pintype "passive"))
    )
    (net (code "33") (name "Net-(EPD_C1-Pad1)") (class "Default")
      (node (ref "EPD_C1") (pin "1") (pinfunction "1_1") (pintype "passive"))
      (node (ref "J1") (pin "4") (pinfunction "4_4") (pintype "bidirectional"))
    )
    (net (code "34") (name "Net-(EPD_C2-Pad1)") (class "Default")
      (node (ref "EPD_C2") (pin "1") (pinfunction "1_1") (pintype "passive"))
      (node (ref "J1") (pin "5") (pinfunction "5_5") (pintype "bidirectional"))
    )
    (net (code "35") (name "Net-(EPD_C6-Pad1)") (class "Default")
      (node (ref "EPD_C6") (pin "1") (pinfunction "1_1") (pintype "passive"))
      (node (ref "J1") (pin "18") (pinfunction "18_18") (pintype "bidirectional"))
    )
    (net (code "36") (name "Net-(EPD_C7-Pad1)") (class "Default")
      (node (ref "EPD_C7") (pin "1") (pinfunction "1_1") (pintype "passive"))
      (node (ref "J1") (pin "19") (pinfunction "19_19") (pintype "bidirectional"))
    )
    (net (code "37") (name "Net-(EPD_C8-Pad1)") (class "Default")
      (node (ref "EPD_C8") (pin "1") (pinfunction "1_1") (pintype "passive"))
      (node (ref "J1") (pin "20") (pinfunction "20_20") (pintype "bidirectional"))
    )
    (net (code "38") (name "Net-(EPD_C10-Pad1)") (class "Default")
      (node (ref "EPD_C10") (pin "1") (pinfunction "1_1") (pintype "passive"))
      (node (ref "J1") (pin "22") (pinfunction "22_22") (pintype "bidirectional"))
    )
    (net (code "39") (name "Net-(EPD_C12-Pad1)") (class "Default")
      (node (ref "EPD_C12") (pin "1") (pinfunction "1_1") (pintype "passive"))
      (node (ref "J1") (pin "24") (pinfunction "24_24") (pintype "bidirectional"))
    )
    (net (code "40") (name "Net-(IC1-CT)") (class "Default")
      (node (ref "C_DELAY") (pin "1") (pinfunction "1_1") (pintype "passive"))
      (node (ref "IC1") (pin "5") (pinfunction "CT_5") (pintype "bidirectional"))
    )
    (net (code "41") (name "Net-(J2-PadA5)") (class "Default")
      (node (ref "J2") (pin "A5") (pinfunction "A5_A5") (pintype "bidirectional"))
      (node (ref "R2-USB1") (pin "2") (pinfunction "2_2") (pintype "passive"))
    )
    (net (code "42") (name "Net-(J2-PadB5)") (class "Default")
      (node (ref "J2") (pin "B5") (pinfunction "B5_B5") (pintype "bidirectional"))
      (node (ref "R2-USB") (pin "1") (pinfunction "1_1") (pintype "passive"))
    )
    (net (code "43") (name "Net-(U5-PROG)") (class "Default")
      (node (ref "R2_BAT") (pin "2") (pinfunction "2_2") (pintype "passive"))
      (node (ref "U5") (pin "5") (pinfunction "PROG_5") (pintype "input"))
    )
    (net (code "44") (name "Net-(U5-STAT)") (class "Default")
      (node (ref "R1_BAT") (pin "2") (pinfunction "2_2") (pintype "passive"))
      (node (ref "U5") (pin "1") (pinfunction "STAT_1") (pintype "output"))
    )
    (net (code "45") (name "PREVGH") (class "Default")
      (node (ref "D5") (pin "1") (pinfunction "K_1") (pintype "bidirectional"))
      (node (ref "EPD_C9") (pin "1") (pinfunction "1_1") (pintype "passive"))
      (node (ref "J1") (pin "21") (pinfunction "21_21") (pintype "bidirectional"))
    )
    (net (code "46") (name "PREVGL") (class "Default")
      (node (ref "D4") (pin "2") (pinfunction "A_2") (pintype "bidirectional"))
      (node (ref "EPD_C11") (pin "1") (pinfunction "1_1") (pintype "passive"))
      (node (ref "J1") (pin "23") (pinfunction "23_23") (pintype "bidirectional"))
    )
    (net (code "47") (name "RESE") (class "Default")
      (node (ref "J1") (pin "3") (pinfunction "3_3") (pintype "bidirectional"))
      (node (ref "Q3") (pin "2") (pinfunction "S_2") (pintype "bidirectional"))
      (node (ref "R3") (pin "2") (pinfunction "2_2") (pintype "passive"))
    )
    (net (code "48") (name "RESE'") (class "Default")
      (node (ref "R2") (pin "2") (pinfunction "2_2") (pintype "passive"))
      (node (ref "R3") (pin "1") (pinfunction "1_1") (pintype "passive"))
      (node (ref "SJ1") (pin "2") (pinfunction "2_2") (pintype "passive"))
    )
    (net (code "49") (name "RESET") (class "Default")
      (node (ref "C5") (pin "1") (pinfunction "1_1") (pintype "passive"))
      (node (ref "IC1") (pin "1") (pinfunction "VOUT_1") (pintype "bidirectional"))
      (node (ref "RESET_BUTTON") (pin "3") (pinfunction "3_3") (pintype "passive"))
      (node (ref "RESET_BUTTON") (pin "4") (pinfunction "4_4") (pintype "passive"))
      (node (ref "R_RESET") (pin "1") (pinfunction "1_1") (pintype "passive"))
      (node (ref "U2") (pin "3") (pinfunction "EN_3") (pintype "input"))
    )
    (net (code "50") (name "RTC_RST") (class "Default")
      (node (ref "U2") (pin "16") (pinfunction "IO18_16") (pintype "bidirectional"))
      (node (ref "U3") (pin "4") (pinfunction "~{RST}_4") (pintype "input"))
    )
    (net (code "51") (name "RX") (class "Default")
      (node (ref "TP2") (pin "TP") (pinfunction "TP_TP") (pintype "input"))
      (node (ref "U2") (pin "24") (pinfunction "RXD0/GPIO17_24") (pintype "bidirectional"))
    )
    (net (code "52") (name "SCK") (class "Default")
      (node (ref "J1") (pin "13") (pinfunction "13_13") (pintype "bidirectional"))
      (node (ref "J4") (pin "P5") (pinfunction "CLK_P5") (pintype "bidirectional"))
      (node (ref "TP8") (pin "TP") (pinfunction "TP_TP") (pintype "input"))
      (node (ref "U1") (pin "6") (pinfunction "CLK_6") (pintype "input"))
      (node (ref "U2") (pin "6") (pinfunction "IO6_6") (pintype "bidirectional"))
    )
    (net (code "53") (name "SCL") (class "Default")
      (node (ref "J3") (pin "4") (pinfunction "4_4") (pintype "passive"))
      (node (ref "R2-PINH") (pin "2") (pinfunction "2_2") (pintype "passive"))
      (node (ref "SENSOR2") (pin "4") (pinfunction "SCK_4") (pintype "input"))
      (node (ref "U2") (pin "20") (pinfunction "IO22_20") (pintype "bidirectional"))
      (node (ref "U3") (pin "16") (pinfunction "SCL_16") (pintype "input"))
      (node (ref "U4") (pin "7") (pinfunction "SCL_7") (pintype "input"))
    )
    (net (code "54") (name "SDA") (class "Default")
      (node (ref "J3") (pin "3") (pinfunction "3_3") (pintype "passive"))
      (node (ref "R1_PINH") (pin "2") (pinfunction "2_2") (pintype "passive"))
      (node (ref "SENSOR2") (pin "3") (pinfunction "SDI_3") (pintype "bidirectional"))
      (node (ref "U2") (pin "19") (pinfunction "IO21_19") (pintype "bidirectional"))
      (node (ref "U3") (pin "15") (pinfunction "SDA_15") (pintype "bidirectional"))
      (node (ref "U4") (pin "8") (pinfunction "SDA_8") (pintype "bidirectional"))
    )
    (net (code "55") (name "SRC") (class "Default")
      (node (ref "C4") (pin "2") (pinfunction "2_2") (pintype "passive"))
      (node (ref "D5") (pin "2") (pinfunction "A_2") (pintype "bidirectional"))
      (node (ref "L1") (pin "1") (pinfunction "1_1") (pintype "passive"))
      (node (ref "Q3") (pin "3") (pinfunction "D_3") (pintype "bidirectional"))
    )
    (net (code "56") (name "SS_SD") (class "Default")
      (node (ref "J4") (pin "P2") (pinfunction "CD/DAT3_P2") (pintype "bidirectional"))
      (node (ref "U2") (pin "4") (pinfunction "IO4_4") (pintype "bidirectional"))
    )
    (net (code "57") (name "TX") (class "Default")
      (node (ref "TP1") (pin "TP") (pinfunction "TP_TP") (pintype "input"))
      (node (ref "U2") (pin "25") (pinfunction "TXD0/GPIO16_25") (pintype "bidirectional"))
    )
    (net (code "58") (name "USB_D+") (class "Default")
      (node (ref "D1") (pin "1") (pinfunction "I/O1_1_1") (pintype "bidirectional"))
      (node (ref "U2") (pin "14") (pinfunction "IO13_14") (pintype "bidirectional"))
    )
    (net (code "59") (name "USB_D-") (class "Default")
      (node (ref "D1") (pin "3") (pinfunction "I/O2_1_3") (pintype "bidirectional"))
      (node (ref "U2") (pin "13") (pinfunction "IO12_13") (pintype "bidirectional"))
    )
    (net (code "60") (name "VBAT") (class "Default")
      (node (ref "C2_BAT") (pin "1") (pinfunction "1_1") (pintype "passive"))
      (node (ref "Q1") (pin "3") (pinfunction "D_3") (pintype "bidirectional"))
      (node (ref "TP3") (pin "TP") (pinfunction "TP_TP") (pintype "input"))
      (node (ref "U4") (pin "2") (pinfunction "CELL_2") (pintype "power_in"))
      (node (ref "U4") (pin "3") (pinfunction "VDD_3") (pintype "power_in"))
      (node (ref "U5") (pin "3") (pinfunction "VBAT_3") (pintype "power_in"))
    )
    (net (code "61") (name "VBUS") (class "Default")
      (node (ref "C1_BAT") (pin "1") (pinfunction "1_1") (pintype "passive"))
      (node (ref "C4_USB") (pin "1") (pinfunction "1_1") (pintype "passive"))
      (node (ref "C5_USB") (pin "1") (pinfunction "1_1") (pintype "passive"))
      (node (ref "CHG_LED") (pin "A") (pinfunction "A_A") (pintype "passive"))
      (node (ref "D1") (pin "5") (pinfunction "VBUS_5") (pintype "bidirectional"))
      (node (ref "D2") (pin "2") (pinfunction "ANODE_2") (pintype "bidirectional"))
      (node (ref "PFMF.050.1") (pin "2") (pinfunction "2_2") (pintype "passive"))
      (node (ref "Q1") (pin "1") (pinfunction "G_1") (pintype "bidirectional"))
      (node (ref "R1_PWRUSB") (pin "2") (pinfunction "2_2") (pintype "passive"))
      (node (ref "TP14") (pin "TP") (pinfunction "TP_TP") (pintype "input"))
      (node (ref "U5") (pin "4") (pinfunction "VIN_4") (pintype "power_in"))
    )
    (net (code "62") (name "VRTC") (class "Default")
      (node (ref "C10_SUPERCAP") (pin "2") (pinfunction "2_2") (pintype "passive"))
      (node (ref "C8") (pin "1") (pinfunction "1_1") (pintype "passive"))
      (node (ref "R_CAPACITOR") (pin "2") (pinfunction "2_2") (pintype "passive"))
      (node (ref "U3") (pin "14") (pinfunction "VBAT_14") (pintype "power_in"))
    )
    (net (code "63") (name "VUSB") (class "Default")
      (node (ref "J2") (pin "A4") (pinfunction "A4_A4") (pintype "bidirectional"))
      (node (ref "J2") (pin "A9") (pinfunction "A9_A9") (pintype "bidirectional"))
      (node (ref "J2") (pin "B4") (pinfunction "B4_B4") (pintype "bidirectional"))
      (node (ref "J2") (pin "B9") (pinfunction "B9_B9") (pintype "bidirectional"))
      (node (ref "PFMF.050.1") (pin "1") (pinfunction "1_1") (pintype "passive"))
    )
    (net (code "64") (name "unconnected-(IC1-NC-Pad4)") (class "Default")
      (node (ref "IC1") (pin "4") (pinfunction "NC_4") (pintype "no_connect"))
    )
    (net (code "65") (name "unconnected-(IC4-NC-Pad4)") (class "Default")
      (node (ref "IC4") (pin "4") (pinfunction "NC_4") (pintype "no_connect"))
    )
    (net (code "66") (name "unconnected-(J1-Pad1)") (class "Default")
      (node (ref "J1") (pin "1") (pinfunction "1_1") (pintype "bidirectional"))
    )
    (net (code "67") (name "unconnected-(J1-Pad6)") (class "Default")
      (node (ref "J1") (pin "6") (pinfunction "6_6") (pintype "bidirectional"))
    )
    (net (code "68") (name "unconnected-(J1-Pad7)") (class "Default")
      (node (ref "J1") (pin "7") (pinfunction "7_7") (pintype "bidirectional"))
    )
    (net (code "69") (name "unconnected-(J1-PadMP1)") (class "Default")
      (node (ref "J1") (pin "MP1") (pinfunction "MP1_MP1") (pintype "bidirectional"))
    )
    (net (code "70") (name "unconnected-(J1-PadMP2)") (class "Default")
      (node (ref "J1") (pin "MP2") (pinfunction "MP2_MP2") (pintype "bidirectional"))
    )
    (net (code "71") (name "unconnected-(J2-PadA8)") (class "Default")
      (node (ref "J2") (pin "A8") (pinfunction "A8_A8") (pintype "bidirectional"))
    )
    (net (code "72") (name "unconnected-(J2-PadB8)") (class "Default")
      (node (ref "J2") (pin "B8") (pinfunction "B8_B8") (pintype "bidirectional"))
    )
    (net (code "73") (name "unconnected-(J4-DAT1-PadP8)") (class "Default")
      (node (ref "J4") (pin "P8") (pinfunction "DAT1_P8") (pintype "bidirectional"))
    )
    (net (code "74") (name "unconnected-(J4-DAT2-PadP1)") (class "Default")
      (node (ref "J4") (pin "P1") (pinfunction "DAT2_P1") (pintype "bidirectional"))
    )
    (net (code "75") (name "unconnected-(J4-DETECTION_1-PadS1)") (class "Default")
      (node (ref "J4") (pin "S1") (pinfunction "DETECTION_1_S1") (pintype "bidirectional"))
    )
    (net (code "76") (name "unconnected-(J4-DETECTION_2-PadS2)") (class "Default")
      (node (ref "J4") (pin "S2") (pinfunction "DETECTION_2_S2") (pintype "bidirectional"))
    )
    (net (code "77") (name "unconnected-(U2-NC-Pad22)") (class "Default")
      (node (ref "U2") (pin "22") (pinfunction "NC_22") (pintype "no_connect"))
    )
    (net (code "78") (name "unconnected-(U4-~{ALERT}-Pad5)") (class "Default")
      (node (ref "U4") (pin "5") (pinfunction "~{ALERT}_5") (pintype "output"))
    )
  )
)
